# stage1_amp_flat_switch_5V_V1p1.net
KiCad netlist of a schematic drawn in EAGLE
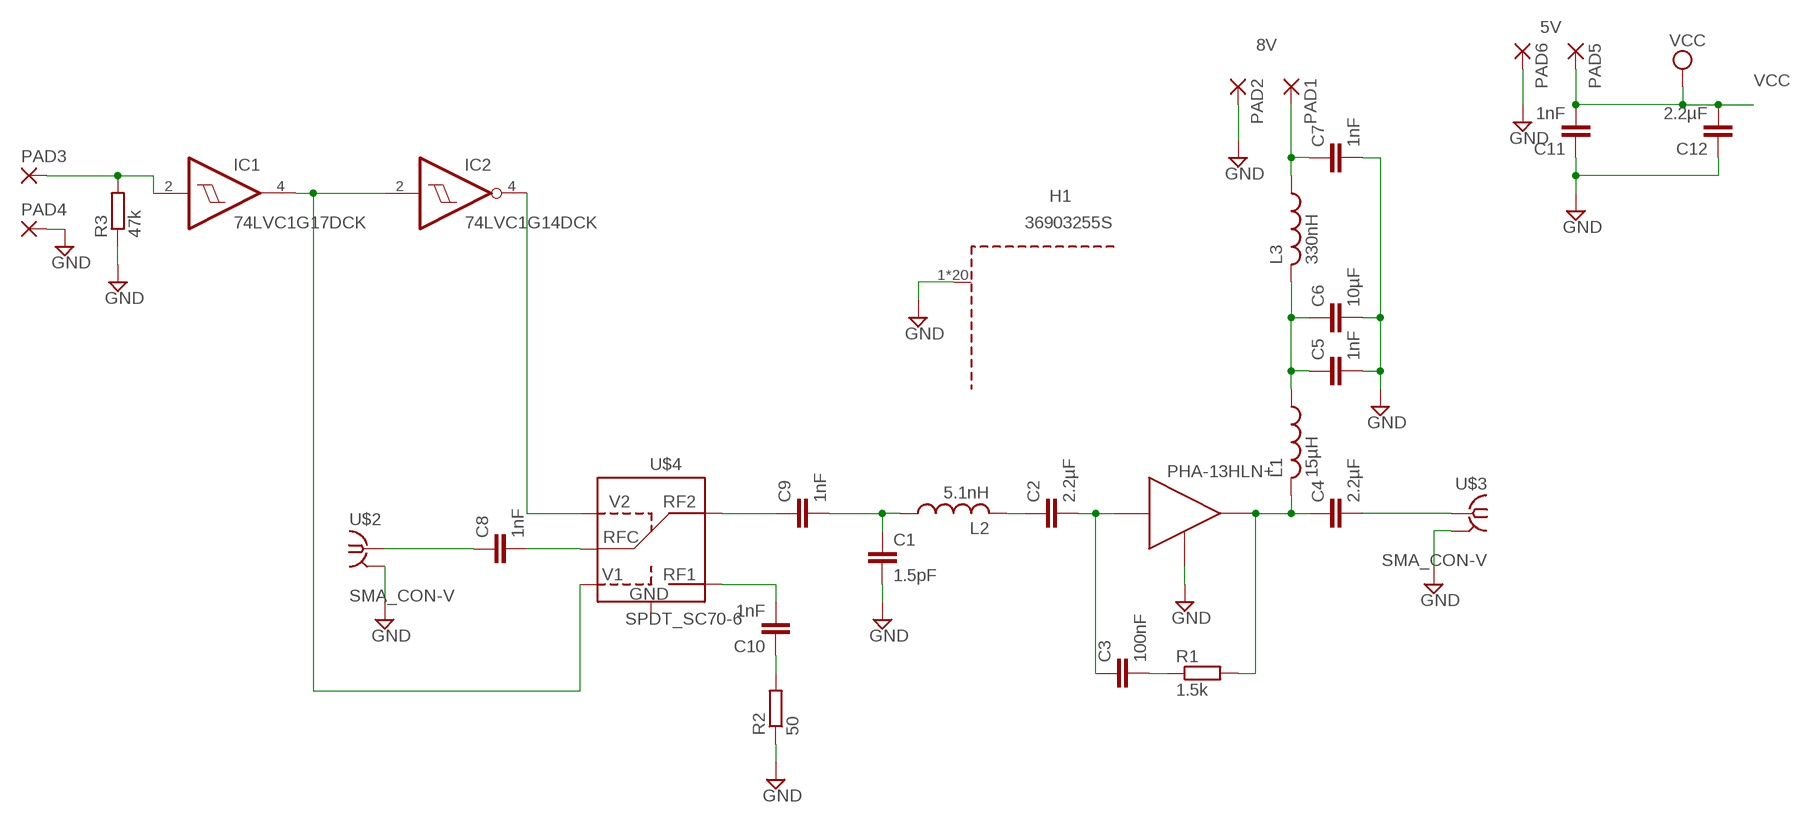
[diagram p0: schematic, sheet 1]

(export (version "E")
  (design (tool "Eeschema 10.0.6"))
  (components
    (comp (ref "C1")
      (value "1.5pF")
      (footprint "eagle-import:C0402")
      (libsource (lib "eagle-import") (part "C-EUC0402"))
    )
    (comp (ref "C2")
      (value "2.2µF")
      (footprint "eagle-import:C0402")
      (libsource (lib "eagle-import") (part "C-EUC0402"))
    )
    (comp (ref "C3")
      (value "100nF")
      (footprint "eagle-import:C0402")
      (libsource (lib "eagle-import") (part "C-EUC0402"))
    )
    (comp (ref "C4")
      (value "2.2µF")
      (footprint "eagle-import:C0402")
      (libsource (lib "eagle-import") (part "C-EUC0402"))
    )
    (comp (ref "C5")
      (value "1nF")
      (footprint "eagle-import:C0402")
      (libsource (lib "eagle-import") (part "C-EUC0402"))
    )
    (comp (ref "C6")
      (value "10µF")
      (footprint "eagle-import:C0805")
      (libsource (lib "eagle-import") (part "C-EUC0805"))
    )
    (comp (ref "C7")
      (value "1nF")
      (footprint "eagle-import:C0402")
      (libsource (lib "eagle-import") (part "C-EUC0402"))
    )
    (comp (ref "C8")
      (value "1nF")
      (footprint "eagle-import:C0402")
      (libsource (lib "eagle-import") (part "C-EUC0402"))
    )
    (comp (ref "C9")
      (value "1nF")
      (footprint "eagle-import:C0402")
      (libsource (lib "eagle-import") (part "C-EUC0402"))
    )
    (comp (ref "C10")
      (value "1nF")
      (footprint "eagle-import:C0402")
      (libsource (lib "eagle-import") (part "C-EUC0402"))
    )
    (comp (ref "C11")
      (value "1nF")
      (footprint "eagle-import:C0402")
      (libsource (lib "eagle-import") (part "C-EUC0402"))
    )
    (comp (ref "C12")
      (value "2.2µF")
      (footprint "eagle-import:C0402")
      (libsource (lib "eagle-import") (part "C-EUC0402"))
    )
    (comp (ref "H1")
      (value "36903255S")
      (footprint "eagle-import:WE-SHC_ONE-PIECE_36903255S")
      (libsource (lib "eagle-import") (part "WE-SHC_ONE-PIECE_36903255S"))
    )
    (comp (ref "IC1")
      (value "74LVC1G17DCK")
      (footprint "eagle-import:SC70-5")
      (libsource (lib "eagle-import") (part "741G17DCKLVC"))
    )
    (comp (ref "IC2")
      (value "74LVC1G14DCK")
      (footprint "eagle-import:SC70-5")
      (libsource (lib "eagle-import") (part "741G14DCKLVC"))
    )
    (comp (ref "L1")
      (value "15µH")
      (footprint "eagle-import:L3225M")
      (libsource (lib "eagle-import") (part "L-USL3225M"))
    )
    (comp (ref "L2")
      (value "5.1nH")
      (footprint "eagle-import:L2012C")
      (libsource (lib "eagle-import") (part "L-USL2012C"))
    )
    (comp (ref "L3")
      (value "330nH")
      (footprint "eagle-import:L3225M")
      (libsource (lib "eagle-import") (part "L-USL3225M"))
    )
    (comp (ref "PAD1")
      (value "SMD5")
      (footprint "eagle-import:SMD2,54-5,08")
      (libsource (lib "eagle-import") (part "SMD5"))
    )
    (comp (ref "PAD2")
      (value "SMD5")
      (footprint "eagle-import:SMD2,54-5,08")
      (libsource (lib "eagle-import") (part "SMD5"))
    )
    (comp (ref "PAD3")
      (value "SMD5")
      (footprint "eagle-import:SMD2,54-5,08")
      (libsource (lib "eagle-import") (part "SMD5"))
    )
    (comp (ref "PAD4")
      (value "SMD5")
      (footprint "eagle-import:SMD2,54-5,08")
      (libsource (lib "eagle-import") (part "SMD5"))
    )
    (comp (ref "PAD5")
      (value "SMD5")
      (footprint "eagle-import:SMD2,54-5,08")
      (libsource (lib "eagle-import") (part "SMD5"))
    )
    (comp (ref "PAD6")
      (value "SMD5")
      (footprint "eagle-import:SMD2,54-5,08")
      (libsource (lib "eagle-import") (part "SMD5"))
    )
    (comp (ref "R1")
      (value "1.5k")
      (footprint "eagle-import:R0402")
      (libsource (lib "eagle-import") (part "R-EU_R0402"))
    )
    (comp (ref "R2")
      (value "50")
      (footprint "eagle-import:R0402")
      (libsource (lib "eagle-import") (part "R-EU_R0402"))
    )
    (comp (ref "R3")
      (value "47k")
      (footprint "eagle-import:R0805")
      (libsource (lib "eagle-import") (part "R-EU_R0805"))
    )
    (comp (ref "U$1")
      (value "PHA-13HLN+")
      (footprint "eagle-import:SOT89")
      (libsource (lib "eagle-import") (part "TQP3M9008SOT-89"))
    )
    (comp (ref "U$2")
      (value "SMA_CON-V")
      (footprint "eagle-import:BU-SMA-V")
      (libsource (lib "eagle-import") (part "SMA_CON-V"))
    )
    (comp (ref "U$3")
      (value "SMA_CON-V")
      (footprint "eagle-import:BU-SMA-V")
      (libsource (lib "eagle-import") (part "SMA_CON-V"))
    )
    (comp (ref "U$4")
      (value "SPDT_SC70-6")
      (footprint "eagle-import:SC70-6")
      (libsource (lib "eagle-import") (part "SPDT_SC70-6"))
    )
  )
  (nets
    (net (code "1") (name "GND") (class "Default")
      (node (ref "C1") (pin "2") (pinfunction "2_2") (pintype "passive"))
      (node (ref "C11") (pin "1") (pinfunction "1_1") (pintype "passive"))
      (node (ref "C12") (pin "1") (pinfunction "1_1") (pintype "passive"))
      (node (ref "C5") (pin "2") (pinfunction "2_2") (pintype "passive"))
      (node (ref "C6") (pin "2") (pinfunction "2_2") (pintype "passive"))
      (node (ref "C7") (pin "2") (pinfunction "2_2") (pintype "passive"))
      (node (ref "H1") (pin "1") (pinfunction "GND_1") (pintype "power_in"))
      (node (ref "H1") (pin "10") (pinfunction "GND_10") (pintype "power_in"))
      (node (ref "H1") (pin "11") (pinfunction "GND_11") (pintype "power_in"))
      (node (ref "H1") (pin "12") (pinfunction "GND_12") (pintype "power_in"))
      (node (ref "H1") (pin "13") (pinfunction "GND_13") (pintype "power_in"))
      (node (ref "H1") (pin "14") (pinfunction "GND_14") (pintype "power_in"))
      (node (ref "H1") (pin "15") (pinfunction "GND_15") (pintype "power_in"))
      (node (ref "H1") (pin "16") (pinfunction "GND_16") (pintype "power_in"))
      (node (ref "H1") (pin "17") (pinfunction "GND_17") (pintype "power_in"))
      (node (ref "H1") (pin "18") (pinfunction "GND_18") (pintype "power_in"))
      (node (ref "H1") (pin "19") (pinfunction "GND_19") (pintype "power_in"))
      (node (ref "H1") (pin "2") (pinfunction "GND_2") (pintype "power_in"))
      (node (ref "H1") (pin "20") (pinfunction "GND_20") (pintype "power_in"))
      (node (ref "H1") (pin "3") (pinfunction "GND_3") (pintype "power_in"))
      (node (ref "H1") (pin "4") (pinfunction "GND_4") (pintype "power_in"))
      (node (ref "H1") (pin "5") (pinfunction "GND_5") (pintype "power_in"))
      (node (ref "H1") (pin "6") (pinfunction "GND_6") (pintype "power_in"))
      (node (ref "H1") (pin "7") (pinfunction "GND_7") (pintype "power_in"))
      (node (ref "H1") (pin "8") (pinfunction "GND_8") (pintype "power_in"))
      (node (ref "H1") (pin "9") (pinfunction "GND_9") (pintype "power_in"))
      (node (ref "PAD2") (pin "1") (pinfunction "P_1") (pintype "passive"))
      (node (ref "PAD4") (pin "1") (pinfunction "P_1") (pintype "passive"))
      (node (ref "PAD6") (pin "1") (pinfunction "P_1") (pintype "passive"))
      (node (ref "R2") (pin "1") (pinfunction "1_1") (pintype "passive"))
      (node (ref "R3") (pin "1") (pinfunction "1_1") (pintype "passive"))
      (node (ref "U$1") (pin "2") (pinfunction "GND_2") (pintype "bidirectional"))
      (node (ref "U$1") (pin "2@1") (pinfunction "GND_2@1") (pintype "bidirectional"))
      (node (ref "U$2") (pin "2") (pinfunction "GND_2") (pintype "passive"))
      (node (ref "U$2") (pin "3") (pinfunction "GND_3") (pintype "passive"))
      (node (ref "U$2") (pin "4") (pinfunction "GND_4") (pintype "passive"))
      (node (ref "U$2") (pin "5") (pinfunction "GND_5") (pintype "passive"))
      (node (ref "U$3") (pin "2") (pinfunction "GND_2") (pintype "passive"))
      (node (ref "U$3") (pin "3") (pinfunction "GND_3") (pintype "passive"))
      (node (ref "U$3") (pin "4") (pinfunction "GND_4") (pintype "passive"))
      (node (ref "U$3") (pin "5") (pinfunction "GND_5") (pintype "passive"))
    )
    (net (code "2") (name "Net-(C1-Pad1)") (class "Default")
      (node (ref "C1") (pin "1") (pinfunction "1_1") (pintype "passive"))
      (node (ref "C9") (pin "2") (pinfunction "2_2") (pintype "passive"))
      (node (ref "L2") (pin "1") (pinfunction "1_1") (pintype "passive"))
    )
    (net (code "3") (name "Net-(C2-Pad1)") (class "Default")
      (node (ref "C2") (pin "1") (pinfunction "1_1") (pintype "passive"))
      (node (ref "L2") (pin "2") (pinfunction "2_2") (pintype "passive"))
    )
    (net (code "4") (name "Net-(C3-Pad2)") (class "Default")
      (node (ref "C3") (pin "2") (pinfunction "2_2") (pintype "passive"))
      (node (ref "R1") (pin "1") (pinfunction "1_1") (pintype "passive"))
    )
    (net (code "5") (name "Net-(C4-Pad2)") (class "Default")
      (node (ref "C4") (pin "2") (pinfunction "2_2") (pintype "passive"))
      (node (ref "U$3") (pin "1") (pinfunction "1_1") (pintype "passive"))
    )
    (net (code "6") (name "Net-(C5-Pad1)") (class "Default")
      (node (ref "C5") (pin "1") (pinfunction "1_1") (pintype "passive"))
      (node (ref "C6") (pin "1") (pinfunction "1_1") (pintype "passive"))
      (node (ref "L1") (pin "1") (pinfunction "1_1") (pintype "passive"))
      (node (ref "L3") (pin "2") (pinfunction "2_2") (pintype "passive"))
    )
    (net (code "7") (name "Net-(C8-Pad1)") (class "Default")
      (node (ref "C8") (pin "1") (pinfunction "1_1") (pintype "passive"))
      (node (ref "U$2") (pin "1") (pinfunction "1_1") (pintype "passive"))
    )
    (net (code "8") (name "Net-(C10-Pad1)") (class "Default")
      (node (ref "C10") (pin "1") (pinfunction "1_1") (pintype "passive"))
      (node (ref "R2") (pin "2") (pinfunction "2_2") (pintype "passive"))
    )
    (net (code "9") (name "Net-(IC1A-I)") (class "Default")
      (node (ref "IC1") (pin "2") (pinfunction "I_2") (pintype "input"))
      (node (ref "PAD3") (pin "1") (pinfunction "P_1") (pintype "passive"))
      (node (ref "R3") (pin "2") (pinfunction "2_2") (pintype "passive"))
    )
    (net (code "10") (name "Net-(IC1A-O)") (class "Default")
      (node (ref "IC1") (pin "4") (pinfunction "O_4") (pintype "output"))
      (node (ref "IC2") (pin "2") (pinfunction "I_2") (pintype "input"))
      (node (ref "U$4") (pin "6") (pinfunction "V1_6") (pintype "bidirectional"))
    )
    (net (code "11") (name "Net-(IC2A-O)") (class "Default")
      (node (ref "IC2") (pin "4") (pinfunction "O_4") (pintype "output"))
      (node (ref "U$4") (pin "4") (pinfunction "V2_4") (pintype "bidirectional"))
    )
    (net (code "12") (name "Net-(PAD1-P)") (class "Default")
      (node (ref "C7") (pin "1") (pinfunction "1_1") (pintype "passive"))
      (node (ref "L3") (pin "1") (pinfunction "1_1") (pintype "passive"))
      (node (ref "PAD1") (pin "1") (pinfunction "P_1") (pintype "passive"))
    )
    (net (code "13") (name "Net-(U$1-IN)") (class "Default")
      (node (ref "C2") (pin "2") (pinfunction "2_2") (pintype "passive"))
      (node (ref "C3") (pin "1") (pinfunction "1_1") (pintype "passive"))
      (node (ref "U$1") (pin "1") (pinfunction "IN_1") (pintype "bidirectional"))
    )
    (net (code "14") (name "Net-(U$1-OUT)") (class "Default")
      (node (ref "C4") (pin "1") (pinfunction "1_1") (pintype "passive"))
      (node (ref "L1") (pin "2") (pinfunction "2_2") (pintype "passive"))
      (node (ref "R1") (pin "2") (pinfunction "2_2") (pintype "passive"))
      (node (ref "U$1") (pin "3") (pinfunction "OUT_3") (pintype "bidirectional"))
    )
    (net (code "15") (name "Net-(U$4-RF1)") (class "Default")
      (node (ref "C10") (pin "2") (pinfunction "2_2") (pintype "passive"))
      (node (ref "U$4") (pin "1") (pinfunction "RF1_1") (pintype "bidirectional"))
    )
    (net (code "16") (name "Net-(U$4-RF2)") (class "Default")
      (node (ref "C9") (pin "1") (pinfunction "1_1") (pintype "passive"))
      (node (ref "U$4") (pin "3") (pinfunction "RF2_3") (pintype "bidirectional"))
    )
    (net (code "17") (name "Net-(U$4-RFC)") (class "Default")
      (node (ref "C8") (pin "2") (pinfunction "2_2") (pintype "passive"))
      (node (ref "U$4") (pin "5") (pinfunction "RFC_5") (pintype "bidirectional"))
    )
    (net (code "18") (name "VCC") (class "Default")
      (node (ref "C11") (pin "2") (pinfunction "2_2") (pintype "passive"))
      (node (ref "C12") (pin "2") (pinfunction "2_2") (pintype "passive"))
      (node (ref "PAD5") (pin "1") (pinfunction "P_1") (pintype "passive"))
    )
    (net (code "19") (name "unconnected-(U$4-GND-Pad2)") (class "Default")
      (node (ref "U$4") (pin "2") (pinfunction "GND_2") (pintype "bidirectional"))
    )
  )
)
